# MCU_V3_1.net
KiCad netlist of a schematic drawn in Altium Designer
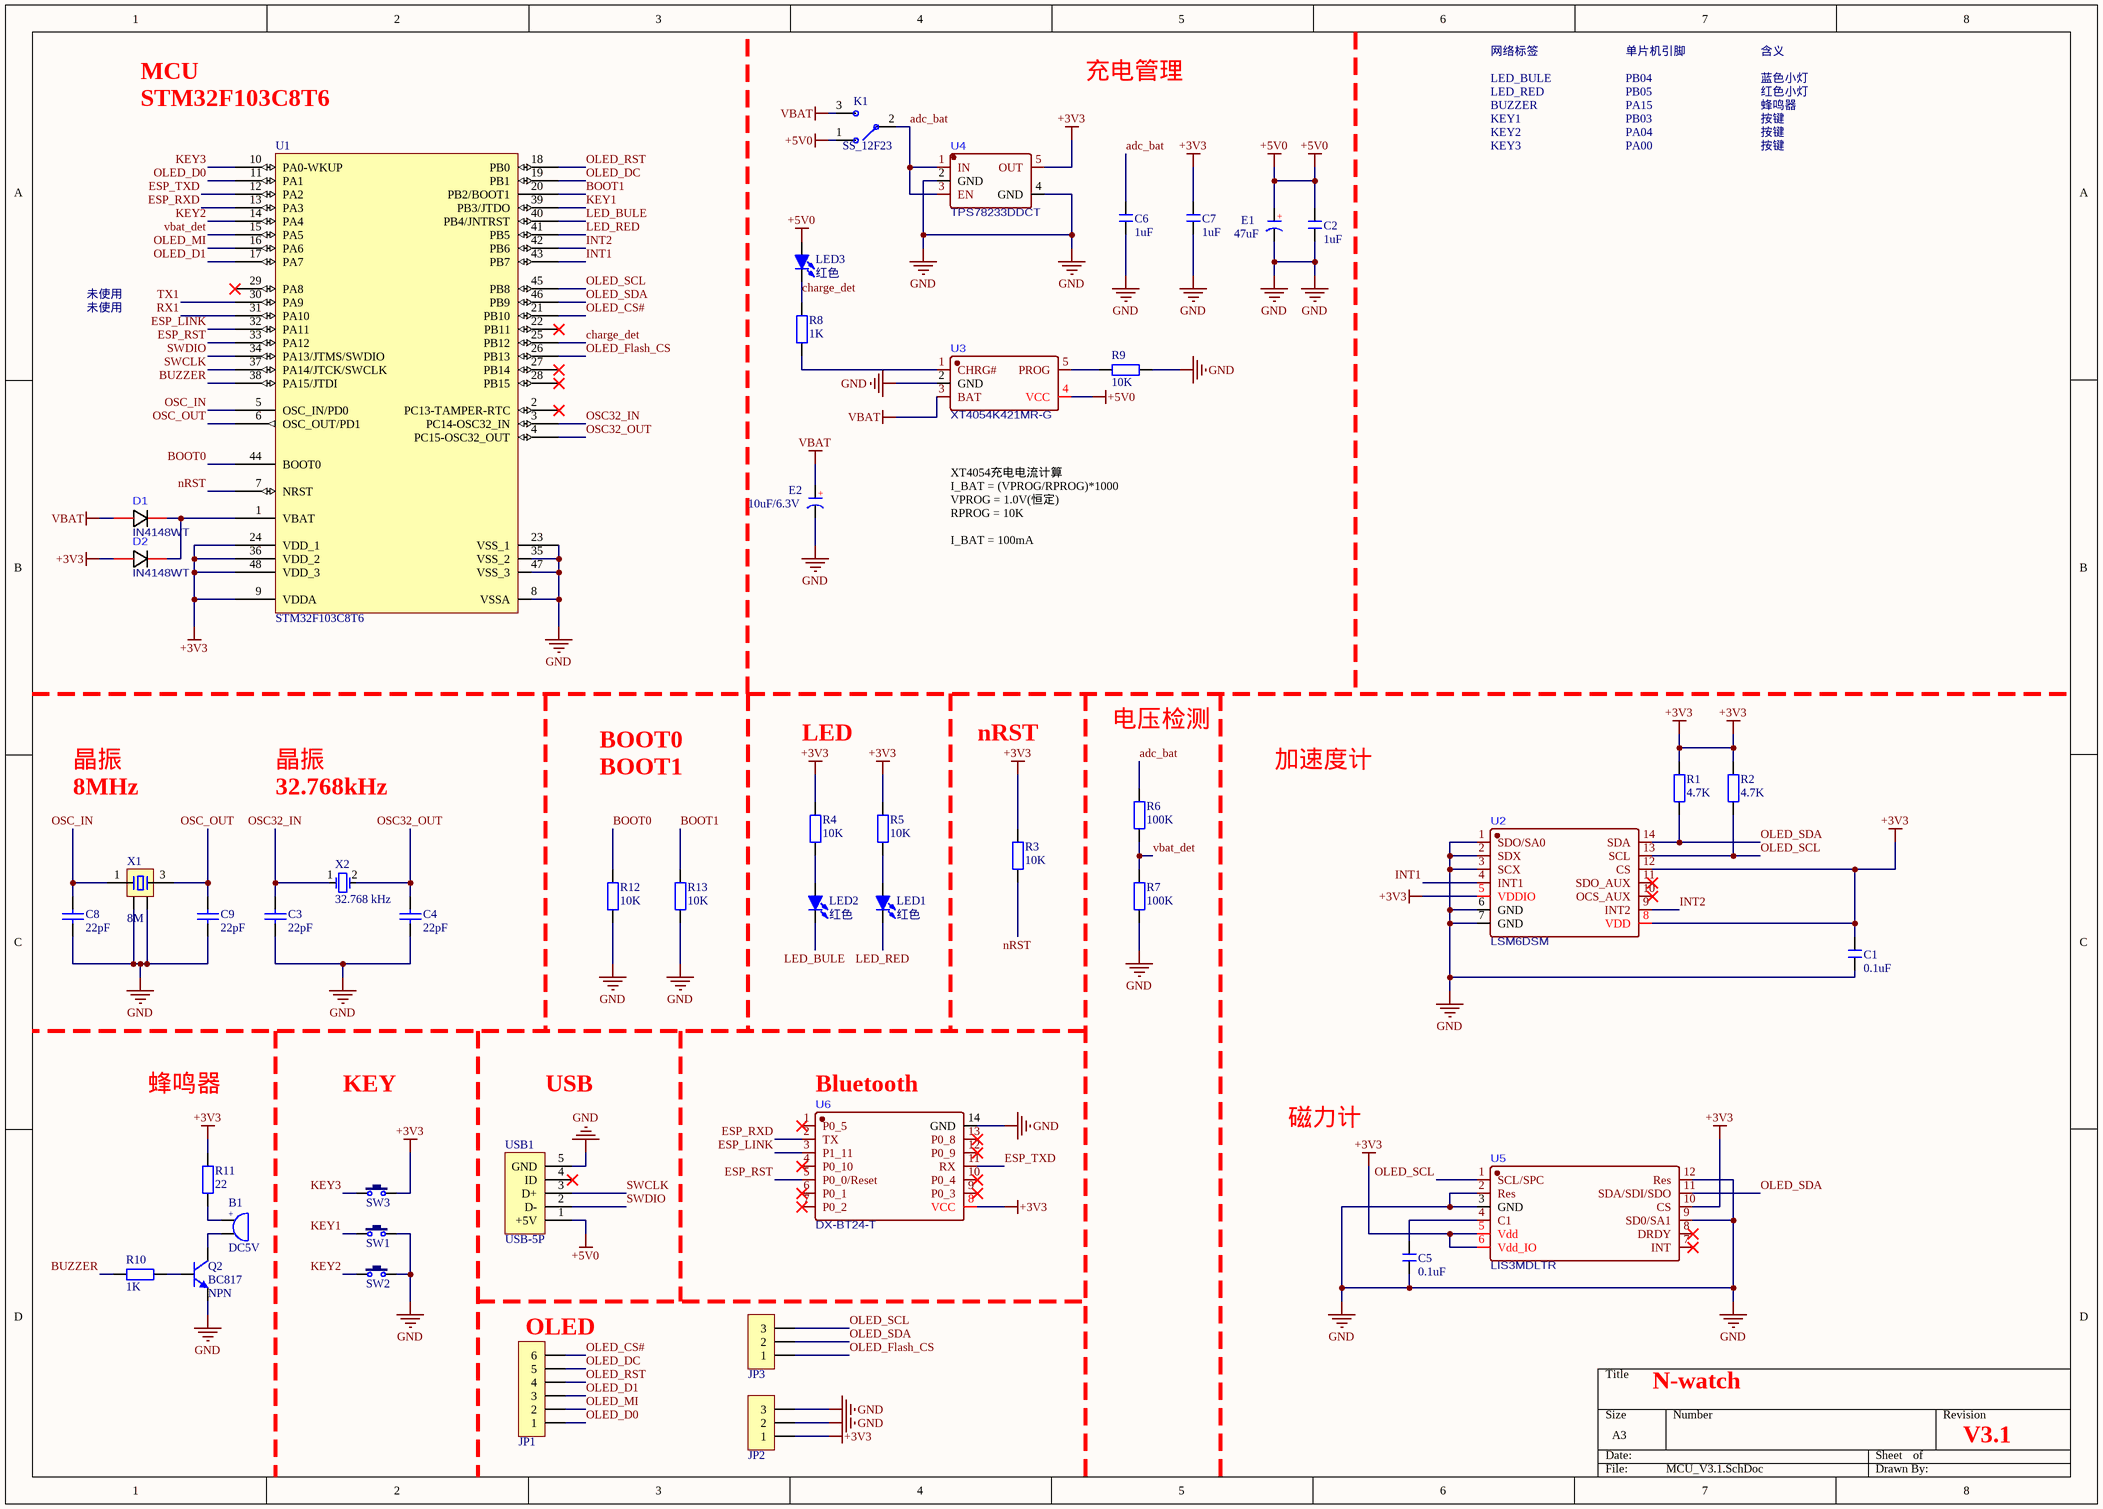
[diagram p0: MCU_V3.1.SchDoc]

(export (version "E")
  (design (tool "Eeschema 10.0.6"))
  (components
    (comp (ref "B1")
      (value "DC5V")
      (footprint "蜂鸣器5020")
      (description "蜂鸣器")
      (fields (field (name "版权归属") "黎明电子style"))
      (libsource (lib "未分类器件") (part "BEEP"))
    )
    (comp (ref "C1")
      (value "0.1uF")
      (footprint "C 0603")
      (description "无极性贴片电容")
      (fields (field (name "版权归属") "黎明电子style"))
      (libsource (lib "电阻-电容-电感") (part "C"))
    )
    (comp (ref "C2")
      (value "1uF")
      (footprint "C 0603")
      (description "无极性贴片电容")
      (fields (field (name "版权归属") "黎明电子style"))
      (libsource (lib "电阻-电容-电感") (part "C"))
    )
    (comp (ref "C3")
      (value "22pF")
      (footprint "C 0603")
      (description "贴片电容/MLCC电容")
      (libsource (lib "R-L-C-FUSE-XTAL-FB-RX") (part "C"))
    )
    (comp (ref "C4")
      (value "22pF")
      (footprint "C 0603")
      (description "贴片电容/MLCC电容")
      (libsource (lib "R-L-C-FUSE-XTAL-FB-RX") (part "C"))
    )
    (comp (ref "C5")
      (value "0.1uF")
      (footprint "C 0603")
      (description "无极性贴片电容")
      (fields (field (name "版权归属") "黎明电子style"))
      (libsource (lib "电阻-电容-电感") (part "C"))
    )
    (comp (ref "C6")
      (value "1uF")
      (footprint "C 0603")
      (description "无极性贴片电容")
      (fields (field (name "版权归属") "黎明电子style"))
      (libsource (lib "电阻-电容-电感") (part "C"))
    )
    (comp (ref "C7")
      (value "1uF")
      (footprint "C 0603")
      (description "无极性贴片电容")
      (fields (field (name "版权归属") "黎明电子style"))
      (libsource (lib "电阻-电容-电感") (part "C"))
    )
    (comp (ref "C8")
      (value "22pF")
      (footprint "C 0603")
      (description "贴片电容/MLCC电容")
      (libsource (lib "") (part "C_1"))
    )
    (comp (ref "C9")
      (value "22pF")
      (footprint "C 0603")
      (description "贴片电容/MLCC电容")
      (libsource (lib "") (part "C_1"))
    )
    (comp (ref "D1") (value "IN4148WT") (footprint "IN4148WT") (libsource (lib "Schlib1") (part "IN4148WT")))
    (comp (ref "D2") (value "IN4148WT") (footprint "IN4148WT") (libsource (lib "Schlib1") (part "IN4148WT")))
    (comp (ref "E1")
      (value "47uF")
      (footprint "CD A(3216)")
      (description "贴片钽电容")
      (fields (field (name "版权归属") "黎明电子style"))
      (libsource (lib "电阻-电容-电感") (part "C-CD"))
    )
    (comp (ref "E2")
      (value "10uF/6.3V")
      (footprint "CD A(3216)")
      (description "贴片钽电容")
      (fields (field (name "版权归属") "黎明电子style"))
      (libsource (lib "电阻-电容-电感") (part "C-CD"))
    )
    (comp (ref "JP1")
      (value "HDR-1X6")
      (footprint "HDR-1X6")
      (description "6P接插件")
      (fields (field (name "版权归属") "黎明电子style"))
      (libsource (lib "接插件") (part "Header 6"))
    )
    (comp (ref "JP2")
      (value "HDR-1X3")
      (footprint "OLED_3PIN")
      (description "3P接插件")
      (fields (field (name "版权归属") "黎明电子style"))
      (libsource (lib "接插件") (part "Header 3"))
    )
    (comp (ref "JP3")
      (value "HDR-1X3")
      (footprint "OLED_3PIN")
      (description "3P接插件")
      (fields (field (name "版权归属") "黎明电子style"))
      (libsource (lib "接插件") (part "Header 3"))
    )
    (comp (ref "K1") (value "SS_12F23") (footprint "SS_12F23") (libsource (lib "Schlib1") (part "SS_12F23")))
    (comp (ref "LED1")
      (value "红色")
      (footprint "LED 0603G")
      (description "贴片LED")
      (fields (field (name "版权归属") "黎明电子style"))
      (libsource (lib "LED") (part "LED-SMD"))
    )
    (comp (ref "LED2")
      (value "红色")
      (footprint "LED 0603G")
      (description "贴片LED")
      (fields (field (name "版权归属") "黎明电子style"))
      (libsource (lib "LED") (part "LED-SMD"))
    )
    (comp (ref "LED3")
      (value "红色")
      (footprint "LED 0603G")
      (description "贴片LED")
      (fields (field (name "版权归属") "黎明电子style"))
      (libsource (lib "LED") (part "LED-SMD"))
    )
    (comp (ref "Q2")
      (value "BC817")
      (footprint "SOT23-3N")
      (description "高频放大-NPN型")
      (fields (field (name "版权归属") "黎明电子style"))
      (libsource (lib "三极管") (part "8050-SMD"))
    )
    (comp (ref "R1")
      (value "4.7K")
      (footprint "R0603_M")
      (description "贴片电阻")
      (libsource (lib "R-L-C-FUSE-XTAL-FB-RX") (part "R"))
    )
    (comp (ref "R2")
      (value "4.7K")
      (footprint "R0603_M")
      (description "贴片电阻")
      (libsource (lib "R-L-C-FUSE-XTAL-FB-RX") (part "R"))
    )
    (comp (ref "R3")
      (value "10K")
      (footprint "R0603_M")
      (description "贴片电阻")
      (libsource (lib "R-L-C-FUSE-XTAL-FB-RX") (part "R"))
    )
    (comp (ref "R4")
      (value "10K")
      (footprint "R0603_M")
      (description "贴片电阻")
      (libsource (lib "R-L-C-FUSE-XTAL-FB-RX") (part "R"))
    )
    (comp (ref "R5")
      (value "10K")
      (footprint "R0603_M")
      (description "贴片电阻")
      (libsource (lib "R-L-C-FUSE-XTAL-FB-RX") (part "R"))
    )
    (comp (ref "R6")
      (value "100K")
      (footprint "R0603_M")
      (description "贴片电阻")
      (libsource (lib "R-L-C-FUSE-XTAL-FB-RX") (part "R"))
    )
    (comp (ref "R7")
      (value "100K")
      (footprint "R0603_M")
      (description "贴片电阻")
      (libsource (lib "R-L-C-FUSE-XTAL-FB-RX") (part "R"))
    )
    (comp (ref "R8")
      (value "1K")
      (footprint "R0603_M")
      (description "贴片电阻")
      (libsource (lib "R-L-C-FUSE-XTAL-FB-RX") (part "R"))
    )
    (comp (ref "R9")
      (value "10K")
      (footprint "R0603_M")
      (description "贴片电阻")
      (libsource (lib "R-L-C-FUSE-XTAL-FB-RX") (part "R"))
    )
    (comp (ref "R10")
      (value "1K")
      (footprint "R0603_M")
      (description "贴片电阻")
      (libsource (lib "R-L-C-FUSE-XTAL-FB-RX") (part "R"))
    )
    (comp (ref "R11")
      (value "22")
      (footprint "R0603_M")
      (description "贴片电阻")
      (libsource (lib "R-L-C-FUSE-XTAL-FB-RX") (part "R"))
    )
    (comp (ref "R12")
      (value "10K")
      (footprint "R0603_M")
      (description "贴片电阻")
      (libsource (lib "R-L-C-FUSE-XTAL-FB-RX") (part "R"))
    )
    (comp (ref "R13")
      (value "10K")
      (footprint "R0603_M")
      (description "贴片电阻")
      (libsource (lib "R-L-C-FUSE-XTAL-FB-RX") (part "R"))
    )
    (comp (ref "SW1")
      (value "3x6x5")
      (footprint "SB-2*4*3.5")
      (description "3x6轻触开关")
      (fields (field (name "版权归属") "黎明电子style"))
      (libsource (lib "按键-开关") (part "TSW 3x6"))
    )
    (comp (ref "SW2")
      (value "3x6x5")
      (footprint "SB-2*4*3.5")
      (description "3x6轻触开关")
      (fields (field (name "版权归属") "黎明电子style"))
      (libsource (lib "按键-开关") (part "TSW 3x6"))
    )
    (comp (ref "SW3")
      (value "3x6x5")
      (footprint "SB-2*4*3.5")
      (description "3x6轻触开关")
      (fields (field (name "版权归属") "黎明电子style"))
      (libsource (lib "按键-开关") (part "TSW 3x6"))
    )
    (comp (ref "U1")
      (value "STM32F103C8T6")
      (footprint "LQFP48 7X7_N")
      (description "Flaah:64/RAM:20/IO:36")
      (fields (field (name "版权归属") "黎明电子style"))
      (libsource (lib "STM32系列单片机") (part "STM32F103C8T6"))
    )
    (comp (ref "U2") (value "LSM6DSM") (footprint "LSM6DSM") (libsource (lib "Schlib1") (part "LSM6DSM")))
    (comp (ref "U3")
      (value "XT4054K421MR-G")
      (footprint "SOT-23-5_L3.0-W1.7-P0.95-LS2.8-BR")
      (libsource (lib "Schlib1") (part "XT4054K421MR-G"))
    )
    (comp (ref "U4")
      (value "TPS78233DDCT")
      (footprint "SOT-23-5_L3.0-W1.7-P0.95-LS2.8-BR")
      (libsource (lib "Schlib1") (part "TPS78233DDCT"))
    )
    (comp (ref "U5")
      (value "LIS3MDLTR")
      (footprint "LIS3MDLTR")
      (libsource (lib "Schlib1") (part "LIS3MDLTR"))
    )
    (comp (ref "U6")
      (value "DX-BT24-T")
      (footprint "DX-BT24-T")
      (libsource (lib "Schlib1") (part "DX-BT24-T"))
    )
    (comp (ref "USB1")
      (value "USB-5P")
      (footprint "MICRO-USB")
      (description "微型USB母座")
      (fields (field (name "版权归属") "黎明电子style"))
      (libsource (lib "接口类") (part "USB-5P"))
    )
    (comp (ref "X1")
      (value "8M")
      (footprint "XTAL-3225")
      (description "4脚晶振")
      (fields (field (name "版权归属") "源创客"))
      (libsource (lib "Schlib1") (part "XTAL-4"))
    )
    (comp (ref "X2")
      (value "32.768 kHz")
      (footprint "XTAL-3215")
      (description "Crystal Oscillator")
      (fields (field (name "PUBLISHER") "Altium Limited"))
      (libsource (lib "Schlib1") (part "XTAL"))
    )
  )
  (nets
    (net (code "1") (name "+3V3") (class "Default")
      (node (ref "C1") (pin "2") (pinfunction "2_2") (pintype "passive"))
      (node (ref "C7") (pin "2") (pinfunction "2_2") (pintype "passive"))
      (node (ref "D2") (pin "1") (pinfunction "1_1") (pintype "passive"))
      (node (ref "JP2") (pin "1") (pinfunction "1_1") (pintype "passive"))
      (node (ref "R1") (pin "2") (pinfunction "2_2") (pintype "passive"))
      (node (ref "R11") (pin "2") (pinfunction "2_2") (pintype "passive"))
      (node (ref "R2") (pin "2") (pinfunction "2_2") (pintype "passive"))
      (node (ref "R3") (pin "2") (pinfunction "2_2") (pintype "passive"))
      (node (ref "R4") (pin "2") (pinfunction "2_2") (pintype "passive"))
      (node (ref "R5") (pin "2") (pinfunction "2_2") (pintype "passive"))
      (node (ref "SW3") (pin "2") (pinfunction "2_2") (pintype "passive"))
      (node (ref "U1") (pin "24") (pinfunction "VDD_1_24") (pintype "power_in"))
      (node (ref "U1") (pin "36") (pinfunction "VDD_2_36") (pintype "power_in"))
      (node (ref "U1") (pin "48") (pinfunction "VDD_3_48") (pintype "power_in"))
      (node (ref "U1") (pin "9") (pinfunction "VDDA_9") (pintype "power_in"))
      (node (ref "U2") (pin "12") (pinfunction "CS_12") (pintype "passive"))
      (node (ref "U2") (pin "5") (pinfunction "VDDIO_5") (pintype "passive"))
      (node (ref "U2") (pin "8") (pinfunction "VDD_8") (pintype "passive"))
      (node (ref "U4") (pin "5") (pinfunction "OUT_5") (pintype "passive"))
      (node (ref "U5") (pin "10") (pinfunction "CS_10") (pintype "passive"))
      (node (ref "U5") (pin "5") (pinfunction "Vdd_5") (pintype "passive"))
      (node (ref "U5") (pin "6") (pinfunction "Vdd_IO_6") (pintype "passive"))
      (node (ref "U6") (pin "8") (pinfunction "VCC_8") (pintype "passive"))
    )
    (net (code "2") (name "+5V0") (class "Default")
      (node (ref "C2") (pin "2") (pinfunction "2_2") (pintype "passive"))
      (node (ref "E1") (pin "1") (pinfunction "A_1") (pintype "passive"))
      (node (ref "K1") (pin "1") (pinfunction "1_1") (pintype "passive"))
      (node (ref "LED3") (pin "1") (pinfunction "A_1") (pintype "passive"))
      (node (ref "U3") (pin "4") (pinfunction "VCC_4") (pintype "passive"))
      (node (ref "USB1") (pin "1") (pinfunction "+5V_1") (pintype "passive"))
    )
    (net (code "4") (name "/BOOT0") (class "Default")
      (node (ref "R12") (pin "2") (pinfunction "2_2") (pintype "passive"))
      (node (ref "U1") (pin "44") (pinfunction "BOOT0_44") (pintype "passive"))
    )
    (net (code "5") (name "/BOOT1") (class "Default")
      (node (ref "R13") (pin "2") (pinfunction "2_2") (pintype "passive"))
      (node (ref "U1") (pin "20") (pinfunction "PB2/BOOT1_20") (pintype "passive"))
    )
    (net (code "6") (name "/BUZZER") (class "Default")
      (node (ref "R10") (pin "2") (pinfunction "2_2") (pintype "passive"))
      (node (ref "U1") (pin "38") (pinfunction "PA15/JTDI_38") (pintype "bidirectional"))
    )
    (net (code "7") (name "/ESP_LINK") (class "Default")
      (node (ref "U1") (pin "32") (pinfunction "PA11_32") (pintype "bidirectional"))
      (node (ref "U6") (pin "3") (pinfunction "P1_11_3") (pintype "passive"))
    )
    (net (code "8") (name "/ESP_RST") (class "Default")
      (node (ref "U1") (pin "33") (pinfunction "PA12_33") (pintype "bidirectional"))
      (node (ref "U6") (pin "5") (pinfunction "P0_0/Reset_5") (pintype "passive"))
    )
    (net (code "9") (name "/ESP_RXD") (class "Default")
      (node (ref "U1") (pin "13") (pinfunction "PA3_13") (pintype "bidirectional"))
      (node (ref "U6") (pin "2") (pinfunction "TX_2") (pintype "passive"))
    )
    (net (code "10") (name "/ESP_TXD") (class "Default")
      (node (ref "U1") (pin "12") (pinfunction "PA2_12") (pintype "bidirectional"))
      (node (ref "U6") (pin "11") (pinfunction "RX_11") (pintype "passive"))
    )
    (net (code "11") (name "/INT1") (class "Default")
      (node (ref "U1") (pin "43") (pinfunction "PB7_43") (pintype "bidirectional"))
      (node (ref "U2") (pin "4") (pinfunction "INT1_4") (pintype "passive"))
    )
    (net (code "12") (name "/INT2") (class "Default")
      (node (ref "U1") (pin "42") (pinfunction "PB6_42") (pintype "bidirectional"))
      (node (ref "U2") (pin "9") (pinfunction "INT2_9") (pintype "passive"))
    )
    (net (code "13") (name "/KEY1") (class "Default")
      (node (ref "SW1") (pin "1") (pinfunction "1_1") (pintype "passive"))
      (node (ref "U1") (pin "39") (pinfunction "PB3/JTDO_39") (pintype "bidirectional"))
    )
    (net (code "14") (name "/KEY2") (class "Default")
      (node (ref "SW2") (pin "1") (pinfunction "1_1") (pintype "passive"))
      (node (ref "U1") (pin "14") (pinfunction "PA4_14") (pintype "bidirectional"))
    )
    (net (code "15") (name "/KEY3") (class "Default")
      (node (ref "SW3") (pin "1") (pinfunction "1_1") (pintype "passive"))
      (node (ref "U1") (pin "10") (pinfunction "PA0-WKUP_10") (pintype "bidirectional"))
    )
    (net (code "16") (name "/LED_BULE") (class "Default")
      (node (ref "LED2") (pin "2") (pinfunction "K_2") (pintype "passive"))
      (node (ref "U1") (pin "40") (pinfunction "PB4/JNTRST_40") (pintype "bidirectional"))
    )
    (net (code "17") (name "/LED_RED") (class "Default")
      (node (ref "LED1") (pin "2") (pinfunction "K_2") (pintype "passive"))
      (node (ref "U1") (pin "41") (pinfunction "PB5_41") (pintype "bidirectional"))
    )
    (net (code "18") (name "/OLED_CS#") (class "Default")
      (node (ref "JP1") (pin "6") (pinfunction "6_6") (pintype "passive"))
      (node (ref "U1") (pin "21") (pinfunction "PB10_21") (pintype "bidirectional"))
    )
    (net (code "19") (name "/OLED_D0") (class "Default")
      (node (ref "JP1") (pin "1") (pinfunction "1_1") (pintype "passive"))
      (node (ref "U1") (pin "11") (pinfunction "PA1_11") (pintype "bidirectional"))
    )
    (net (code "20") (name "/OLED_D1") (class "Default")
      (node (ref "JP1") (pin "3") (pinfunction "3_3") (pintype "passive"))
      (node (ref "U1") (pin "17") (pinfunction "PA7_17") (pintype "bidirectional"))
    )
    (net (code "21") (name "/OLED_DC") (class "Default")
      (node (ref "JP1") (pin "5") (pinfunction "5_5") (pintype "passive"))
      (node (ref "U1") (pin "19") (pinfunction "PB1_19") (pintype "bidirectional"))
    )
    (net (code "22") (name "/OLED_Flash_CS") (class "Default")
      (node (ref "JP3") (pin "1") (pinfunction "1_1") (pintype "passive"))
      (node (ref "U1") (pin "26") (pinfunction "PB13_26") (pintype "bidirectional"))
    )
    (net (code "23") (name "/OLED_MI") (class "Default")
      (node (ref "JP1") (pin "2") (pinfunction "2_2") (pintype "passive"))
      (node (ref "U1") (pin "16") (pinfunction "PA6_16") (pintype "bidirectional"))
    )
    (net (code "24") (name "/OLED_RST") (class "Default")
      (node (ref "JP1") (pin "4") (pinfunction "4_4") (pintype "passive"))
      (node (ref "U1") (pin "18") (pinfunction "PB0_18") (pintype "bidirectional"))
    )
    (net (code "25") (name "/OLED_SCL") (class "Default")
      (node (ref "JP3") (pin "3") (pinfunction "3_3") (pintype "passive"))
      (node (ref "R2") (pin "1") (pinfunction "1_1") (pintype "passive"))
      (node (ref "U1") (pin "45") (pinfunction "PB8_45") (pintype "bidirectional"))
      (node (ref "U2") (pin "13") (pinfunction "SCL_13") (pintype "passive"))
      (node (ref "U5") (pin "1") (pinfunction "SCL/SPC_1") (pintype "passive"))
    )
    (net (code "26") (name "/OLED_SDA") (class "Default")
      (node (ref "JP3") (pin "2") (pinfunction "2_2") (pintype "passive"))
      (node (ref "R1") (pin "1") (pinfunction "1_1") (pintype "passive"))
      (node (ref "U1") (pin "46") (pinfunction "PB9_46") (pintype "bidirectional"))
      (node (ref "U2") (pin "14") (pinfunction "SDA_14") (pintype "passive"))
      (node (ref "U5") (pin "11") (pinfunction "SDA/SDI/SDO_11") (pintype "passive"))
    )
    (net (code "27") (name "/OSC32_IN") (class "Default")
      (node (ref "C3") (pin "1") (pinfunction "1_1") (pintype "passive"))
      (node (ref "U1") (pin "3") (pinfunction "PC14-OSC32_IN_3") (pintype "bidirectional"))
      (node (ref "X2") (pin "1") (pinfunction "OSC1_1") (pintype "passive"))
    )
    (net (code "28") (name "/OSC32_OUT") (class "Default")
      (node (ref "C4") (pin "1") (pinfunction "1_1") (pintype "passive"))
      (node (ref "U1") (pin "4") (pinfunction "PC15-OSC32_OUT_4") (pintype "bidirectional"))
      (node (ref "X2") (pin "2") (pinfunction "OSC2_2") (pintype "passive"))
    )
    (net (code "29") (name "/OSC_IN") (class "Default")
      (node (ref "C8") (pin "2") (pinfunction "2_2") (pintype "passive"))
      (node (ref "U1") (pin "5") (pinfunction "OSC_IN/PD0_5") (pintype "passive"))
      (node (ref "X1") (pin "1") (pinfunction "1_1") (pintype "passive"))
    )
    (net (code "30") (name "/OSC_OUT") (class "Default")
      (node (ref "C9") (pin "2") (pinfunction "2_2") (pintype "passive"))
      (node (ref "U1") (pin "6") (pinfunction "OSC_OUT/PD1_6") (pintype "output"))
      (node (ref "X1") (pin "3") (pinfunction "3_3") (pintype "passive"))
    )
    (net (code "31") (name "/RX1") (class "Default")
      (node (ref "U1") (pin "31") (pinfunction "PA10_31") (pintype "bidirectional"))
    )
    (net (code "32") (name "/SWCLK") (class "Default")
      (node (ref "U1") (pin "37") (pinfunction "PA14/JTCK/SWCLK_37") (pintype "bidirectional"))
      (node (ref "USB1") (pin "3") (pinfunction "D+_3") (pintype "passive"))
    )
    (net (code "33") (name "/SWDIO") (class "Default")
      (node (ref "U1") (pin "34") (pinfunction "PA13/JTMS/SWDIO_34") (pintype "bidirectional"))
      (node (ref "USB1") (pin "2") (pinfunction "D-_2") (pintype "passive"))
    )
    (net (code "34") (name "/TX1") (class "Default")
      (node (ref "U1") (pin "30") (pinfunction "PA9_30") (pintype "bidirectional"))
    )
    (net (code "35") (name "/adc_bat") (class "Default")
      (node (ref "C6") (pin "2") (pinfunction "2_2") (pintype "passive"))
      (node (ref "K1") (pin "2") (pinfunction "2_2") (pintype "passive"))
      (node (ref "R6") (pin "2") (pinfunction "2_2") (pintype "passive"))
      (node (ref "U4") (pin "1") (pinfunction "IN_1") (pintype "passive"))
      (node (ref "U4") (pin "3") (pinfunction "EN_3") (pintype "passive"))
    )
    (net (code "36") (name "/charge_det") (class "Default")
      (node (ref "LED3") (pin "2") (pinfunction "K_2") (pintype "passive"))
      (node (ref "R8") (pin "2") (pinfunction "2_2") (pintype "passive"))
      (node (ref "U1") (pin "25") (pinfunction "PB12_25") (pintype "bidirectional"))
    )
    (net (code "37") (name "/nRST") (class "Default")
      (node (ref "R3") (pin "1") (pinfunction "1_1") (pintype "passive"))
      (node (ref "U1") (pin "7") (pinfunction "NRST_7") (pintype "bidirectional"))
    )
    (net (code "38") (name "/vbat_det") (class "Default")
      (node (ref "R6") (pin "1") (pinfunction "1_1") (pintype "passive"))
      (node (ref "R7") (pin "2") (pinfunction "2_2") (pintype "passive"))
      (node (ref "U1") (pin "15") (pinfunction "PA5_15") (pintype "bidirectional"))
    )
    (net (code "39") (name "GND") (class "Default")
      (node (ref "C1") (pin "1") (pinfunction "1_1") (pintype "passive"))
      (node (ref "C2") (pin "1") (pinfunction "1_1") (pintype "passive"))
      (node (ref "C3") (pin "2") (pinfunction "2_2") (pintype "passive"))
      (node (ref "C4") (pin "2") (pinfunction "2_2") (pintype "passive"))
      (node (ref "C5") (pin "1") (pinfunction "1_1") (pintype "passive"))
      (node (ref "C6") (pin "1") (pinfunction "1_1") (pintype "passive"))
      (node (ref "C7") (pin "1") (pinfunction "1_1") (pintype "passive"))
      (node (ref "C8") (pin "1") (pinfunction "1_1") (pintype "passive"))
      (node (ref "C9") (pin "1") (pinfunction "1_1") (pintype "passive"))
      (node (ref "E1") (pin "2") (pinfunction "K_2") (pintype "passive"))
      (node (ref "E2") (pin "2") (pinfunction "K_2") (pintype "passive"))
      (node (ref "JP2") (pin "2") (pinfunction "2_2") (pintype "passive"))
      (node (ref "JP2") (pin "3") (pinfunction "3_3") (pintype "passive"))
      (node (ref "Q2") (pin "2") (pinfunction "E_2") (pintype "passive"))
      (node (ref "R12") (pin "1") (pinfunction "1_1") (pintype "passive"))
      (node (ref "R13") (pin "1") (pinfunction "1_1") (pintype "passive"))
      (node (ref "R7") (pin "1") (pinfunction "1_1") (pintype "passive"))
      (node (ref "R9") (pin "1") (pinfunction "1_1") (pintype "passive"))
      (node (ref "SW1") (pin "2") (pinfunction "2_2") (pintype "passive"))
      (node (ref "SW2") (pin "2") (pinfunction "2_2") (pintype "passive"))
      (node (ref "U1") (pin "23") (pinfunction "VSS_1_23") (pintype "power_in"))
      (node (ref "U1") (pin "35") (pinfunction "VSS_2_35") (pintype "power_in"))
      (node (ref "U1") (pin "47") (pinfunction "VSS_3_47") (pintype "power_in"))
      (node (ref "U1") (pin "8") (pinfunction "VSSA_8") (pintype "power_in"))
      (node (ref "U2") (pin "1") (pinfunction "SDO/SA0_1") (pintype "passive"))
      (node (ref "U2") (pin "2") (pinfunction "SDX_2") (pintype "passive"))
      (node (ref "U2") (pin "3") (pinfunction "SCX_3") (pintype "passive"))
      (node (ref "U2") (pin "6") (pinfunction "GND_6") (pintype "passive"))
      (node (ref "U2") (pin "7") (pinfunction "GND_7") (pintype "passive"))
      (node (ref "U3") (pin "2") (pinfunction "GND_2") (pintype "passive"))
      (node (ref "U4") (pin "2") (pinfunction "GND_2") (pintype "passive"))
      (node (ref "U4") (pin "4") (pinfunction "GND_4") (pintype "passive"))
      (node (ref "U5") (pin "12") (pinfunction "Res_12") (pintype "passive"))
      (node (ref "U5") (pin "2") (pinfunction "Res_2") (pintype "passive"))
      (node (ref "U5") (pin "3") (pinfunction "GND_3") (pintype "passive"))
      (node (ref "U5") (pin "9") (pinfunction "SD0/SA1_9") (pintype "passive"))
      (node (ref "U6") (pin "14") (pinfunction "GND_14") (pintype "passive"))
      (node (ref "USB1") (pin "5") (pinfunction "GND_5") (pintype "passive"))
      (node (ref "X1") (pin "2") (pinfunction "2_2") (pintype "passive"))
      (node (ref "X1") (pin "4") (pinfunction "4_4") (pintype "passive"))
    )
    (net (code "40") (name "Net-(B1-Pad1)") (class "Default")
      (node (ref "B1") (pin "1") (pinfunction "1_1") (pintype "passive"))
      (node (ref "R11") (pin "1") (pinfunction "1_1") (pintype "passive"))
    )
    (net (code "41") (name "Net-(LED1-A)") (class "Default")
      (node (ref "LED1") (pin "1") (pinfunction "A_1") (pintype "passive"))
      (node (ref "R5") (pin "1") (pinfunction "1_1") (pintype "passive"))
    )
    (net (code "42") (name "Net-(LED2-A)") (class "Default")
      (node (ref "LED2") (pin "1") (pinfunction "A_1") (pintype "passive"))
      (node (ref "R4") (pin "1") (pinfunction "1_1") (pintype "passive"))
    )
    (net (code "43") (name "Net-(Q2-B)") (class "Default")
      (node (ref "Q2") (pin "1") (pinfunction "B_1") (pintype "passive"))
      (node (ref "R10") (pin "1") (pinfunction "1_1") (pintype "passive"))
    )
    (net (code "44") (name "Net-(Q2-C)") (class "Default")
      (node (ref "B1") (pin "2") (pinfunction "2_2") (pintype "passive"))
      (node (ref "Q2") (pin "3") (pinfunction "C_3") (pintype "passive"))
    )
    (net (code "45") (name "Net-(U1-VBAT)") (class "Default")
      (node (ref "D1") (pin "2") (pinfunction "2_2") (pintype "passive"))
      (node (ref "D2") (pin "2") (pinfunction "2_2") (pintype "passive"))
      (node (ref "U1") (pin "1") (pinfunction "VBAT_1") (pintype "power_in"))
    )
    (net (code "46") (name "Net-(U3-CHRG#)") (class "Default")
      (node (ref "R8") (pin "1") (pinfunction "1_1") (pintype "passive"))
      (node (ref "U3") (pin "1") (pinfunction "CHRG#_1") (pintype "passive"))
    )
    (net (code "47") (name "Net-(U3-PROG)") (class "Default")
      (node (ref "R9") (pin "2") (pinfunction "2_2") (pintype "passive"))
      (node (ref "U3") (pin "5") (pinfunction "PROG_5") (pintype "passive"))
    )
    (net (code "48") (name "Net-(U5-C1)") (class "Default")
      (node (ref "C5") (pin "2") (pinfunction "2_2") (pintype "passive"))
      (node (ref "U5") (pin "4") (pinfunction "C1_4") (pintype "passive"))
    )
    (net (code "49") (name "VBAT") (class "Default")
      (node (ref "D1") (pin "1") (pinfunction "1_1") (pintype "passive"))
      (node (ref "E2") (pin "1") (pinfunction "A_1") (pintype "passive"))
      (node (ref "K1") (pin "3") (pinfunction "3_3") (pintype "passive"))
      (node (ref "U3") (pin "3") (pinfunction "BAT_3") (pintype "passive"))
    )
    (net (code "50") (name "unconnected-(U1-PA8-Pad29)") (class "Default")
      (node (ref "U1") (pin "29") (pinfunction "PA8_29") (pintype "bidirectional+no_connect"))
    )
    (net (code "51") (name "unconnected-(U1-PB11-Pad22)") (class "Default")
      (node (ref "U1") (pin "22") (pinfunction "PB11_22") (pintype "bidirectional+no_connect"))
    )
    (net (code "52") (name "unconnected-(U1-PB14-Pad27)") (class "Default")
      (node (ref "U1") (pin "27") (pinfunction "PB14_27") (pintype "bidirectional+no_connect"))
    )
    (net (code "53") (name "unconnected-(U1-PB15-Pad28)") (class "Default")
      (node (ref "U1") (pin "28") (pinfunction "PB15_28") (pintype "bidirectional+no_connect"))
    )
    (net (code "54") (name "unconnected-(U1-PC13-TAMPER-RTC-Pad2)") (class "Default")
      (node (ref "U1") (pin "2") (pinfunction "PC13-TAMPER-RTC_2") (pintype "bidirectional+no_connect"))
    )
    (net (code "55") (name "unconnected-(U2-OCS_AUX-Pad10)") (class "Default")
      (node (ref "U2") (pin "10") (pinfunction "OCS_AUX_10") (pintype "passive+no_connect"))
    )
    (net (code "56") (name "unconnected-(U2-SDO_AUX-Pad11)") (class "Default")
      (node (ref "U2") (pin "11") (pinfunction "SDO_AUX_11") (pintype "passive+no_connect"))
    )
    (net (code "57") (name "unconnected-(U5-DRDY-Pad8)") (class "Default")
      (node (ref "U5") (pin "8") (pinfunction "DRDY_8") (pintype "passive+no_connect"))
    )
    (net (code "58") (name "unconnected-(U5-INT-Pad7)") (class "Default")
      (node (ref "U5") (pin "7") (pinfunction "INT_7") (pintype "passive+no_connect"))
    )
    (net (code "59") (name "unconnected-(U6-P0_1-Pad6)") (class "Default")
      (node (ref "U6") (pin "6") (pinfunction "P0_1_6") (pintype "passive+no_connect"))
    )
    (net (code "60") (name "unconnected-(U6-P0_2-Pad7)") (class "Default")
      (node (ref "U6") (pin "7") (pinfunction "P0_2_7") (pintype "passive+no_connect"))
    )
    (net (code "61") (name "unconnected-(U6-P0_3-Pad9)") (class "Default")
      (node (ref "U6") (pin "9") (pinfunction "P0_3_9") (pintype "passive+no_connect"))
    )
    (net (code "62") (name "unconnected-(U6-P0_4-Pad10)") (class "Default")
      (node (ref "U6") (pin "10") (pinfunction "P0_4_10") (pintype "passive+no_connect"))
    )
    (net (code "63") (name "unconnected-(U6-P0_5-Pad1)") (class "Default")
      (node (ref "U6") (pin "1") (pinfunction "P0_5_1") (pintype "passive+no_connect"))
    )
    (net (code "64") (name "unconnected-(U6-P0_8-Pad13)") (class "Default")
      (node (ref "U6") (pin "13") (pinfunction "P0_8_13") (pintype "passive+no_connect"))
    )
    (net (code "65") (name "unconnected-(U6-P0_9-Pad12)") (class "Default")
      (node (ref "U6") (pin "12") (pinfunction "P0_9_12") (pintype "passive+no_connect"))
    )
    (net (code "66") (name "unconnected-(U6-P0_10-Pad4)") (class "Default")
      (node (ref "U6") (pin "4") (pinfunction "P0_10_4") (pintype "passive+no_connect"))
    )
    (net (code "67") (name "unconnected-(USB1-ID-Pad4)") (class "Default")
      (node (ref "USB1") (pin "4") (pinfunction "ID_4") (pintype "passive+no_connect"))
    )
  )
)
